# gnss.net
KiCad netlist of a schematic drawn in EAGLE
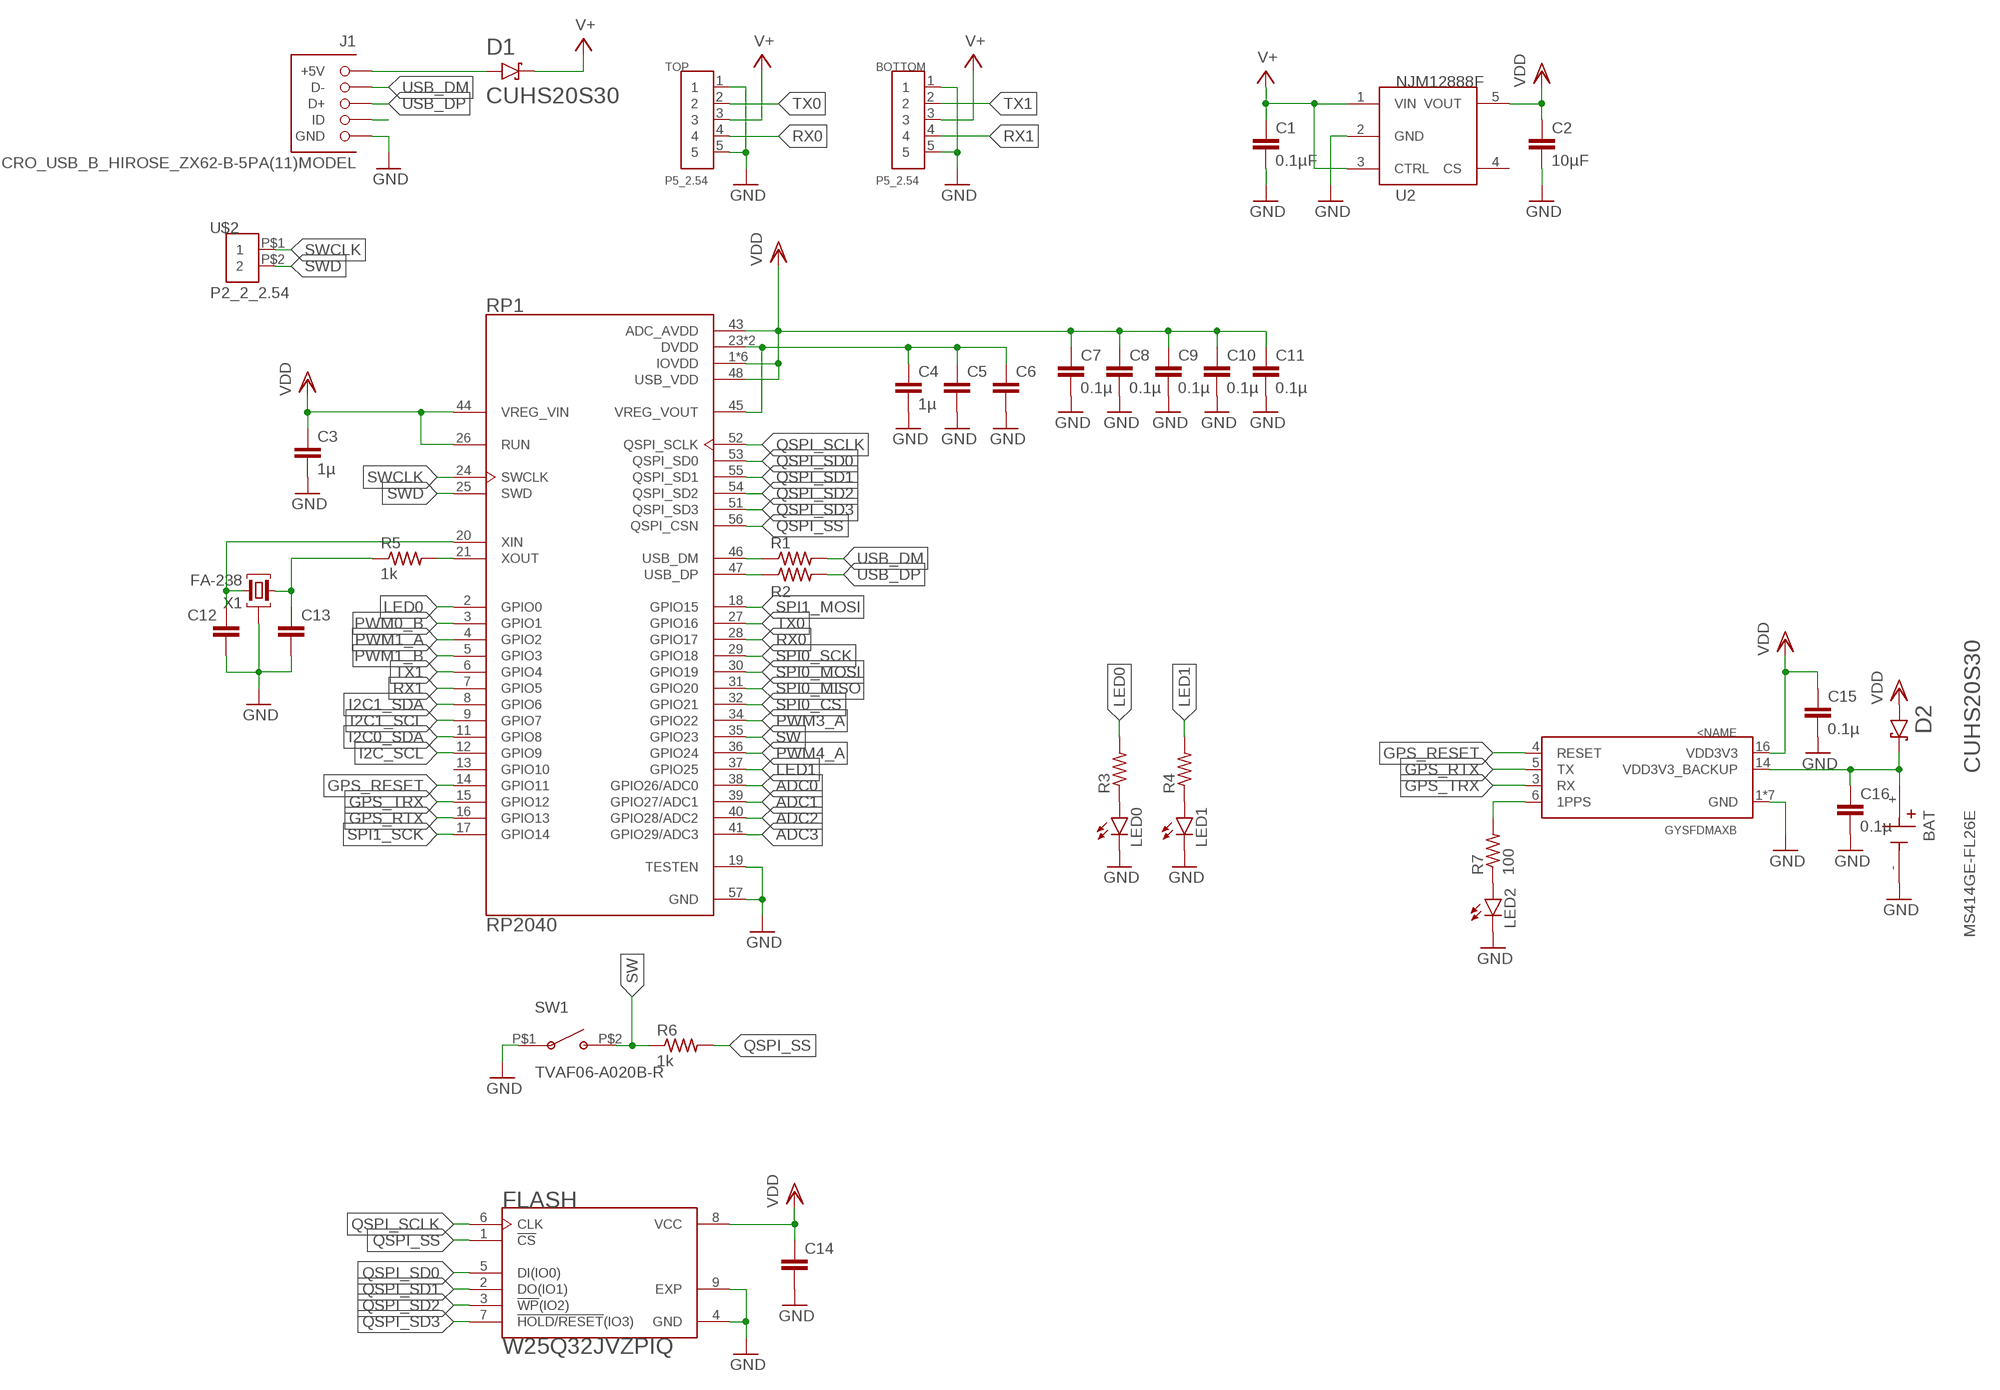
[diagram p0: schematic, sheet 1]

(export (version "E")
  (design (tool "Eeschema 10.0.6"))
  (components
    (comp (ref "BAT")
      (value "MS414GE-FL26E")
      (footprint "eagle-import:BAT_MS414GE-FL26E")
      (fields (field (name "MF") "Seiko"))
      (libsource (lib "eagle-import") (part "MS414GE-FL26E"))
    )
    (comp (ref "BOTTOM")
      (value "P5_2.54")
      (footprint "eagle-import:P5_2.54")
      (libsource (lib "eagle-import") (part "P5_2.54"))
    )
    (comp (ref "C1")
      (value "0.1µF")
      (footprint "eagle-import:C0402")
      (libsource (lib "eagle-import") (part "C-EUC0402"))
    )
    (comp (ref "C2")
      (value "10µF")
      (footprint "eagle-import:C0402")
      (libsource (lib "eagle-import") (part "C-EUC0402"))
    )
    (comp (ref "C3")
      (value "1µ")
      (footprint "eagle-import:C0402")
      (libsource (lib "eagle-import") (part "C-EUC0402"))
    )
    (comp (ref "C4")
      (value "1µ")
      (footprint "eagle-import:C0402")
      (libsource (lib "eagle-import") (part "C-EUC0402"))
    )
    (comp (ref "C5")
      (value "C-EUC0402")
      (footprint "eagle-import:C0402")
      (libsource (lib "eagle-import") (part "C-EUC0402"))
    )
    (comp (ref "C6")
      (value "C-EUC0402")
      (footprint "eagle-import:C0402")
      (libsource (lib "eagle-import") (part "C-EUC0402"))
    )
    (comp (ref "C7")
      (value "0.1µ")
      (footprint "eagle-import:C0402")
      (libsource (lib "eagle-import") (part "C-EUC0402"))
    )
    (comp (ref "C8")
      (value "0.1µ")
      (footprint "eagle-import:C0402")
      (libsource (lib "eagle-import") (part "C-EUC0402"))
    )
    (comp (ref "C9")
      (value "0.1µ")
      (footprint "eagle-import:C0402")
      (libsource (lib "eagle-import") (part "C-EUC0402"))
    )
    (comp (ref "C10")
      (value "0.1µ")
      (footprint "eagle-import:C0402")
      (libsource (lib "eagle-import") (part "C-EUC0402"))
    )
    (comp (ref "C11")
      (value "0.1µ")
      (footprint "eagle-import:C0402")
      (libsource (lib "eagle-import") (part "C-EUC0402"))
    )
    (comp (ref "C12")
      (value "C-EUC0402")
      (footprint "eagle-import:C0402")
      (libsource (lib "eagle-import") (part "C-EUC0402"))
    )
    (comp (ref "C13")
      (value "C-EUC0402")
      (footprint "eagle-import:C0402")
      (libsource (lib "eagle-import") (part "C-EUC0402"))
    )
    (comp (ref "C14")
      (value "C-EUC0402")
      (footprint "eagle-import:C0402")
      (libsource (lib "eagle-import") (part "C-EUC0402"))
    )
    (comp (ref "C15")
      (value "0.1µ")
      (footprint "eagle-import:C0402")
      (libsource (lib "eagle-import") (part "C-EUC0402"))
    )
    (comp (ref "C16")
      (value "0.1µ")
      (footprint "eagle-import:C0402")
      (libsource (lib "eagle-import") (part "C-EUC0402"))
    )
    (comp (ref "D1")
      (value "CUHS20S30")
      (footprint "eagle-import:CUHS20S30")
      (libsource (lib "eagle-import") (part "CUHS20S30"))
    )
    (comp (ref "D2")
      (value "CUHS20S30")
      (footprint "eagle-import:CUHS20S30")
      (libsource (lib "eagle-import") (part "CUHS20S30"))
    )
    (comp (ref "FLASH")
      (value "W25Q32JVZPIQ")
      (footprint "eagle-import:SON127P600X500X80-9N")
      (fields (field (name "MF") "Winbond"))
      (libsource (lib "eagle-import") (part "W25Q32JVZPIQ"))
    )
    (comp (ref "GNSS")
      (value "GYSFDMAXB")
      (footprint "eagle-import:GYSFDMAXB")
      (libsource (lib "eagle-import") (part "GYSFDMAXB"))
    )
    (comp (ref "J1")
      (value "MICRO_USB_B_HIROSE_ZX62-B-5PA(11)MODEL")
      (footprint "eagle-import:GHI-CONNECTORS_10118192-0001LF(MICRO-USB-B-AMPHENOL-FCI)")
      (libsource (lib "eagle-import") (part "MICRO_USB_B_HIROSE_ZX62-B-5PA(11)MODEL"))
    )
    (comp (ref "LED0")
      (value "LEDCHIPLED_0603")
      (footprint "eagle-import:CHIPLED_0603")
      (libsource (lib "eagle-import") (part "LEDCHIPLED_0603"))
    )
    (comp (ref "LED1")
      (value "LEDCHIPLED_0603")
      (footprint "eagle-import:CHIPLED_0603")
      (libsource (lib "eagle-import") (part "LEDCHIPLED_0603"))
    )
    (comp (ref "LED2")
      (value "LEDCHIPLED_0603")
      (footprint "eagle-import:CHIPLED_0603")
      (libsource (lib "eagle-import") (part "LEDCHIPLED_0603"))
    )
    (comp (ref "R1")
      (value "R-US_R0402")
      (footprint "eagle-import:R0402")
      (libsource (lib "eagle-import") (part "R-US_R0402"))
    )
    (comp (ref "R2")
      (value "R-US_R0402")
      (footprint "eagle-import:R0402")
      (libsource (lib "eagle-import") (part "R-US_R0402"))
    )
    (comp (ref "R3")
      (value "R-US_R0402")
      (footprint "eagle-import:R0402")
      (libsource (lib "eagle-import") (part "R-US_R0402"))
    )
    (comp (ref "R4")
      (value "R-US_R0402")
      (footprint "eagle-import:R0402")
      (libsource (lib "eagle-import") (part "R-US_R0402"))
    )
    (comp (ref "R5")
      (value "1k")
      (footprint "eagle-import:R0402")
      (libsource (lib "eagle-import") (part "R-US_R0402"))
    )
    (comp (ref "R6")
      (value "1k")
      (footprint "eagle-import:R0402")
      (libsource (lib "eagle-import") (part "R-US_R0402"))
    )
    (comp (ref "R7")
      (value "100")
      (footprint "eagle-import:R0402")
      (libsource (lib "eagle-import") (part "R-US_R0402"))
    )
    (comp (ref "RP1")
      (value "RP2040")
      (footprint "eagle-import:QFN40P700X700X90-57N")
      (fields (field (name "MF") "Raspberry Pi"))
      (libsource (lib "eagle-import") (part "RP2040"))
    )
    (comp (ref "SW1")
      (value "TVAF06-A020B-R")
      (footprint "eagle-import:TVAF06-A020B-R")
      (libsource (lib "eagle-import") (part "TVAF06-A020B-R"))
    )
    (comp (ref "TOP")
      (value "P5_2.54")
      (footprint "eagle-import:P5_2.54")
      (libsource (lib "eagle-import") (part "P5_2.54"))
    )
    (comp (ref "U$2")
      (value "P2_2_2.54")
      (footprint "eagle-import:P2_2.54")
      (libsource (lib "eagle-import") (part "P2_2_2.54"))
    )
    (comp (ref "U2")
      (value "NJM12888F")
      (footprint "eagle-import:SOT95P240X110-5N")
      (libsource (lib "eagle-import") (part "NJM12888F"))
    )
    (comp (ref "X1")
      (value "FA-238")
      (footprint "eagle-import:FA-238")
      (libsource (lib "eagle-import") (part "FA-238"))
    )
  )
  (nets
    (net (code "1") (name "ADC0") (class "Default")
      (node (ref "RP1") (pin "38") (pinfunction "GPIO26/ADC0_38") (pintype "bidirectional"))
    )
    (net (code "2") (name "ADC1") (class "Default")
      (node (ref "RP1") (pin "39") (pinfunction "GPIO27/ADC1_39") (pintype "bidirectional"))
    )
    (net (code "3") (name "ADC2") (class "Default")
      (node (ref "RP1") (pin "40") (pinfunction "GPIO28/ADC2_40") (pintype "bidirectional"))
    )
    (net (code "4") (name "ADC3") (class "Default")
      (node (ref "RP1") (pin "41") (pinfunction "GPIO29/ADC3_41") (pintype "bidirectional"))
    )
    (net (code "5") (name "GND") (class "Default")
      (node (ref "BAT") (pin "-") (pinfunction "-_-") (pintype "passive"))
      (node (ref "BOTTOM") (pin "1") (pinfunction "1_1") (pintype "bidirectional"))
      (node (ref "BOTTOM") (pin "5") (pinfunction "5_5") (pintype "bidirectional"))
      (node (ref "C1") (pin "2") (pinfunction "2_2") (pintype "passive"))
      (node (ref "C10") (pin "2") (pinfunction "2_2") (pintype "passive"))
      (node (ref "C11") (pin "2") (pinfunction "2_2") (pintype "passive"))
      (node (ref "C12") (pin "2") (pinfunction "2_2") (pintype "passive"))
      (node (ref "C13") (pin "2") (pinfunction "2_2") (pintype "passive"))
      (node (ref "C14") (pin "2") (pinfunction "2_2") (pintype "passive"))
      (node (ref "C15") (pin "2") (pinfunction "2_2") (pintype "passive"))
      (node (ref "C16") (pin "2") (pinfunction "2_2") (pintype "passive"))
      (node (ref "C2") (pin "2") (pinfunction "2_2") (pintype "passive"))
      (node (ref "C3") (pin "2") (pinfunction "2_2") (pintype "passive"))
      (node (ref "C4") (pin "2") (pinfunction "2_2") (pintype "passive"))
      (node (ref "C5") (pin "2") (pinfunction "2_2") (pintype "passive"))
      (node (ref "C6") (pin "2") (pinfunction "2_2") (pintype "passive"))
      (node (ref "C7") (pin "2") (pinfunction "2_2") (pintype "passive"))
      (node (ref "C8") (pin "2") (pinfunction "2_2") (pintype "passive"))
      (node (ref "C9") (pin "2") (pinfunction "2_2") (pintype "passive"))
      (node (ref "FLASH") (pin "4") (pinfunction "GND_4") (pintype "power_in"))
      (node (ref "FLASH") (pin "9") (pinfunction "EXP_9") (pintype "passive"))
      (node (ref "GNSS") (pin "1") (pinfunction "GND_1") (pintype "bidirectional"))
      (node (ref "GNSS") (pin "10") (pinfunction "GND_10") (pintype "bidirectional"))
      (node (ref "GNSS") (pin "12") (pinfunction "GND_12") (pintype "bidirectional"))
      (node (ref "GNSS") (pin "19") (pinfunction "GND_19") (pintype "bidirectional"))
      (node (ref "GNSS") (pin "2") (pinfunction "GND_2") (pintype "bidirectional"))
      (node (ref "GNSS") (pin "20") (pinfunction "GND_20") (pintype "bidirectional"))
      (node (ref "GNSS") (pin "7") (pinfunction "GND_7") (pintype "bidirectional"))
      (node (ref "J1") (pin "CGND1") (pinfunction "GND_CGND1") (pintype "bidirectional"))
      (node (ref "J1") (pin "CGND2") (pinfunction "GND_CGND2") (pintype "bidirectional"))
      (node (ref "J1") (pin "CGND3") (pinfunction "GND_CGND3") (pintype "bidirectional"))
      (node (ref "J1") (pin "CGND4") (pinfunction "GND_CGND4") (pintype "bidirectional"))
      (node (ref "J1") (pin "CGND5") (pinfunction "GND_CGND5") (pintype "bidirectional"))
      (node (ref "J1") (pin "CGND6") (pinfunction "GND_CGND6") (pintype "bidirectional"))
      (node (ref "J1") (pin "GND") (pinfunction "GND_GND") (pintype "bidirectional"))
      (node (ref "LED0") (pin "C") (pinfunction "C_C") (pintype "passive"))
      (node (ref "LED1") (pin "C") (pinfunction "C_C") (pintype "passive"))
      (node (ref "LED2") (pin "C") (pinfunction "C_C") (pintype "passive"))
      (node (ref "RP1") (pin "19") (pinfunction "TESTEN_19") (pintype "passive"))
      (node (ref "RP1") (pin "57") (pinfunction "GND_57") (pintype "power_in"))
      (node (ref "SW1") (pin "P$1") (pinfunction "A_P$1") (pintype "bidirectional"))
      (node (ref "TOP") (pin "1") (pinfunction "1_1") (pintype "bidirectional"))
      (node (ref "TOP") (pin "5") (pinfunction "5_5") (pintype "bidirectional"))
      (node (ref "U2") (pin "2") (pinfunction "GND_2") (pintype "power_in"))
      (node (ref "X1") (pin "2") (pinfunction "G_2") (pintype "passive"))
      (node (ref "X1") (pin "4") (pinfunction "G_4") (pintype "passive"))
    )
    (net (code "6") (name "GPS_RESET") (class "Default")
      (node (ref "GNSS") (pin "4") (pinfunction "RESET_4") (pintype "bidirectional"))
      (node (ref "RP1") (pin "14") (pinfunction "GPIO11_14") (pintype "bidirectional"))
    )
    (net (code "7") (name "GPS_RTX") (class "Default")
      (node (ref "GNSS") (pin "5") (pinfunction "TX_5") (pintype "bidirectional"))
      (node (ref "RP1") (pin "16") (pinfunction "GPIO13_16") (pintype "bidirectional"))
    )
    (net (code "8") (name "GPS_TRX") (class "Default")
      (node (ref "GNSS") (pin "3") (pinfunction "RX_3") (pintype "bidirectional"))
      (node (ref "RP1") (pin "15") (pinfunction "GPIO12_15") (pintype "bidirectional"))
    )
    (net (code "9") (name "I2C0_SDA") (class "Default")
      (node (ref "RP1") (pin "11") (pinfunction "GPIO8_11") (pintype "bidirectional"))
    )
    (net (code "10") (name "I2C1_SCL") (class "Default")
      (node (ref "RP1") (pin "9") (pinfunction "GPIO7_9") (pintype "bidirectional"))
    )
    (net (code "11") (name "I2C1_SDA") (class "Default")
      (node (ref "RP1") (pin "8") (pinfunction "GPIO6_8") (pintype "bidirectional"))
    )
    (net (code "12") (name "I2C_SCL") (class "Default")
      (node (ref "RP1") (pin "12") (pinfunction "GPIO9_12") (pintype "bidirectional"))
    )
    (net (code "13") (name "LED0") (class "Default")
      (node (ref "R3") (pin "2") (pinfunction "2_2") (pintype "passive"))
      (node (ref "RP1") (pin "2") (pinfunction "GPIO0_2") (pintype "bidirectional"))
    )
    (net (code "14") (name "LED1") (class "Default")
      (node (ref "R4") (pin "2") (pinfunction "2_2") (pintype "passive"))
      (node (ref "RP1") (pin "37") (pinfunction "GPIO25_37") (pintype "bidirectional"))
    )
    (net (code "15") (name "Net-(C13-Pad1)") (class "Default")
      (node (ref "C13") (pin "1") (pinfunction "1_1") (pintype "passive"))
      (node (ref "R5") (pin "1") (pinfunction "1_1") (pintype "passive"))
      (node (ref "X1") (pin "1") (pinfunction "1_1") (pintype "passive"))
    )
    (net (code "16") (name "Net-(GNSS-1PPS)") (class "Default")
      (node (ref "GNSS") (pin "6") (pinfunction "1PPS_6") (pintype "bidirectional"))
      (node (ref "R7") (pin "2") (pinfunction "2_2") (pintype "passive"))
    )
    (net (code "17") (name "Net-(GNSS-VDD3V3_BACKUP)") (class "Default")
      (node (ref "BAT") (pin "+") (pinfunction "+_+") (pintype "passive"))
      (node (ref "C16") (pin "1") (pinfunction "1_1") (pintype "passive"))
      (node (ref "D2") (pin "C") (pinfunction "C_C") (pintype "bidirectional"))
      (node (ref "GNSS") (pin "14") (pinfunction "VDD3V3_BACKUP_14") (pintype "bidirectional"))
    )
    (net (code "18") (name "Net-(J1-+5V)") (class "Default")
      (node (ref "D1") (pin "A") (pinfunction "A_A") (pintype "bidirectional"))
      (node (ref "J1") (pin "VBUS") (pinfunction "+5V_VBUS") (pintype "bidirectional"))
    )
    (net (code "19") (name "Net-(LED0-PadA)") (class "Default")
      (node (ref "LED0") (pin "A") (pinfunction "A_A") (pintype "passive"))
      (node (ref "R3") (pin "1") (pinfunction "1_1") (pintype "passive"))
    )
    (net (code "20") (name "Net-(LED1-PadA)") (class "Default")
      (node (ref "LED1") (pin "A") (pinfunction "A_A") (pintype "passive"))
      (node (ref "R4") (pin "1") (pinfunction "1_1") (pintype "passive"))
    )
    (net (code "21") (name "Net-(LED2-PadA)") (class "Default")
      (node (ref "LED2") (pin "A") (pinfunction "A_A") (pintype "passive"))
      (node (ref "R7") (pin "1") (pinfunction "1_1") (pintype "passive"))
    )
    (net (code "22") (name "Net-(RP1-USB_DM)") (class "Default")
      (node (ref "R1") (pin "1") (pinfunction "1_1") (pintype "passive"))
      (node (ref "RP1") (pin "46") (pinfunction "USB_DM_46") (pintype "bidirectional"))
    )
    (net (code "23") (name "Net-(RP1-USB_DP)") (class "Default")
      (node (ref "R2") (pin "1") (pinfunction "1_1") (pintype "passive"))
      (node (ref "RP1") (pin "47") (pinfunction "USB_DP_47") (pintype "bidirectional"))
    )
    (net (code "24") (name "Net-(RP1-VREG_VOUT)") (class "Default")
      (node (ref "C4") (pin "1") (pinfunction "1_1") (pintype "passive"))
      (node (ref "C5") (pin "1") (pinfunction "1_1") (pintype "passive"))
      (node (ref "C6") (pin "1") (pinfunction "1_1") (pintype "passive"))
      (node (ref "RP1") (pin "23") (pinfunction "DVDD_23") (pintype "power_in"))
      (node (ref "RP1") (pin "45") (pinfunction "VREG_VOUT_45") (pintype "output"))
      (node (ref "RP1") (pin "50") (pinfunction "DVDD_50") (pintype "power_in"))
    )
    (net (code "25") (name "Net-(RP1-XIN)") (class "Default")
      (node (ref "C12") (pin "1") (pinfunction "1_1") (pintype "passive"))
      (node (ref "RP1") (pin "20") (pinfunction "XIN_20") (pintype "input"))
      (node (ref "X1") (pin "3") (pinfunction "2_3") (pintype "passive"))
    )
    (net (code "26") (name "Net-(RP1-XOUT)") (class "Default")
      (node (ref "R5") (pin "2") (pinfunction "2_2") (pintype "passive"))
      (node (ref "RP1") (pin "21") (pinfunction "XOUT_21") (pintype "output"))
    )
    (net (code "27") (name "PWM0_B") (class "Default")
      (node (ref "RP1") (pin "3") (pinfunction "GPIO1_3") (pintype "bidirectional"))
    )
    (net (code "28") (name "PWM1_A") (class "Default")
      (node (ref "RP1") (pin "4") (pinfunction "GPIO2_4") (pintype "bidirectional"))
    )
    (net (code "29") (name "PWM1_B") (class "Default")
      (node (ref "RP1") (pin "5") (pinfunction "GPIO3_5") (pintype "bidirectional"))
    )
    (net (code "30") (name "PWM3_A") (class "Default")
      (node (ref "RP1") (pin "34") (pinfunction "GPIO22_34") (pintype "bidirectional"))
    )
    (net (code "31") (name "PWM4_A") (class "Default")
      (node (ref "RP1") (pin "36") (pinfunction "GPIO24_36") (pintype "bidirectional"))
    )
    (net (code "32") (name "QSPI_SCLK") (class "Default")
      (node (ref "FLASH") (pin "6") (pinfunction "CLK_6") (pintype "input"))
      (node (ref "RP1") (pin "52") (pinfunction "QSPI_SCLK_52") (pintype "bidirectional"))
    )
    (net (code "33") (name "QSPI_SD0") (class "Default")
      (node (ref "FLASH") (pin "5") (pinfunction "DI(IO0)_5") (pintype "bidirectional"))
      (node (ref "RP1") (pin "53") (pinfunction "QSPI_SD0_53") (pintype "bidirectional"))
    )
    (net (code "34") (name "QSPI_SD1") (class "Default")
      (node (ref "FLASH") (pin "2") (pinfunction "DO(IO1)_2") (pintype "bidirectional"))
      (node (ref "RP1") (pin "55") (pinfunction "QSPI_SD1_55") (pintype "bidirectional"))
    )
    (net (code "35") (name "QSPI_SD2") (class "Default")
      (node (ref "FLASH") (pin "3") (pinfunction "~{WP}(IO2)_3") (pintype "bidirectional"))
      (node (ref "RP1") (pin "54") (pinfunction "QSPI_SD2_54") (pintype "bidirectional"))
    )
    (net (code "36") (name "QSPI_SD3") (class "Default")
      (node (ref "FLASH") (pin "7") (pinfunction "~{HOLD/RESET}(IO3)_7") (pintype "bidirectional"))
      (node (ref "RP1") (pin "51") (pinfunction "QSPI_SD3_51") (pintype "bidirectional"))
    )
    (net (code "37") (name "QSPI_SS") (class "Default")
      (node (ref "FLASH") (pin "1") (pinfunction "~{CS}_1") (pintype "input"))
      (node (ref "R6") (pin "2") (pinfunction "2_2") (pintype "passive"))
      (node (ref "RP1") (pin "56") (pinfunction "QSPI_CSN_56") (pintype "bidirectional"))
    )
    (net (code "38") (name "RX0") (class "Default")
      (node (ref "RP1") (pin "28") (pinfunction "GPIO17_28") (pintype "bidirectional"))
      (node (ref "TOP") (pin "4") (pinfunction "4_4") (pintype "bidirectional"))
    )
    (net (code "39") (name "RX1") (class "Default")
      (node (ref "BOTTOM") (pin "4") (pinfunction "4_4") (pintype "bidirectional"))
      (node (ref "RP1") (pin "7") (pinfunction "GPIO5_7") (pintype "bidirectional"))
    )
    (net (code "40") (name "SPI0_CS") (class "Default")
      (node (ref "RP1") (pin "32") (pinfunction "GPIO21_32") (pintype "bidirectional"))
    )
    (net (code "41") (name "SPI0_MISO") (class "Default")
      (node (ref "RP1") (pin "31") (pinfunction "GPIO20_31") (pintype "bidirectional"))
    )
    (net (code "42") (name "SPI0_MOSI") (class "Default")
      (node (ref "RP1") (pin "30") (pinfunction "GPIO19_30") (pintype "bidirectional"))
    )
    (net (code "43") (name "SPI0_SCK") (class "Default")
      (node (ref "RP1") (pin "29") (pinfunction "GPIO18_29") (pintype "bidirectional"))
    )
    (net (code "44") (name "SPI1_MOSI") (class "Default")
      (node (ref "RP1") (pin "18") (pinfunction "GPIO15_18") (pintype "bidirectional"))
    )
    (net (code "45") (name "SPI1_SCK") (class "Default")
      (node (ref "RP1") (pin "17") (pinfunction "GPIO14_17") (pintype "bidirectional"))
    )
    (net (code "46") (name "SW") (class "Default")
      (node (ref "R6") (pin "1") (pinfunction "1_1") (pintype "passive"))
      (node (ref "RP1") (pin "35") (pinfunction "GPIO23_35") (pintype "bidirectional"))
      (node (ref "SW1") (pin "P$2") (pinfunction "B_P$2") (pintype "bidirectional"))
    )
    (net (code "47") (name "SWCLK") (class "Default")
      (node (ref "RP1") (pin "24") (pinfunction "SWCLK_24") (pintype "input"))
      (node (ref "U$2") (pin "P$1") (pinfunction "1_P$1") (pintype "bidirectional"))
    )
    (net (code "48") (name "SWD") (class "Default")
      (node (ref "RP1") (pin "25") (pinfunction "SWD_25") (pintype "bidirectional"))
      (node (ref "U$2") (pin "P$2") (pinfunction "2_P$2") (pintype "bidirectional"))
    )
    (net (code "49") (name "TX0") (class "Default")
      (node (ref "RP1") (pin "27") (pinfunction "GPIO16_27") (pintype "bidirectional"))
      (node (ref "TOP") (pin "2") (pinfunction "2_2") (pintype "bidirectional"))
    )
    (net (code "50") (name "TX1") (class "Default")
      (node (ref "BOTTOM") (pin "2") (pinfunction "2_2") (pintype "bidirectional"))
      (node (ref "RP1") (pin "6") (pinfunction "GPIO4_6") (pintype "bidirectional"))
    )
    (net (code "51") (name "USB_DM") (class "Default")
      (node (ref "J1") (pin "D-") (pinfunction "D-_D-") (pintype "bidirectional"))
      (node (ref "R1") (pin "2") (pinfunction "2_2") (pintype "passive"))
    )
    (net (code "52") (name "USB_DP") (class "Default")
      (node (ref "J1") (pin "D+") (pinfunction "D+_D+") (pintype "bidirectional"))
      (node (ref "R2") (pin "2") (pinfunction "2_2") (pintype "passive"))
    )
    (net (code "53") (name "V+") (class "Default")
      (node (ref "BOTTOM") (pin "3") (pinfunction "3_3") (pintype "bidirectional"))
      (node (ref "C1") (pin "1") (pinfunction "1_1") (pintype "passive"))
      (node (ref "D1") (pin "C") (pinfunction "C_C") (pintype "bidirectional"))
      (node (ref "TOP") (pin "3") (pinfunction "3_3") (pintype "bidirectional"))
      (node (ref "U2") (pin "1") (pinfunction "VIN_1") (pintype "power_in"))
      (node (ref "U2") (pin "3") (pinfunction "CTRL_3") (pintype "input"))
    )
    (net (code "54") (name "VDD") (class "Default")
      (node (ref "C10") (pin "1") (pinfunction "1_1") (pintype "passive"))
      (node (ref "C11") (pin "1") (pinfunction "1_1") (pintype "passive"))
      (node (ref "C14") (pin "1") (pinfunction "1_1") (pintype "passive"))
      (node (ref "C15") (pin "1") (pinfunction "1_1") (pintype "passive"))
      (node (ref "C2") (pin "1") (pinfunction "1_1") (pintype "passive"))
      (node (ref "C3") (pin "1") (pinfunction "1_1") (pintype "passive"))
      (node (ref "C7") (pin "1") (pinfunction "1_1") (pintype "passive"))
      (node (ref "C8") (pin "1") (pinfunction "1_1") (pintype "passive"))
      (node (ref "C9") (pin "1") (pinfunction "1_1") (pintype "passive"))
      (node (ref "D2") (pin "A") (pinfunction "A_A") (pintype "bidirectional"))
      (node (ref "FLASH") (pin "8") (pinfunction "VCC_8") (pintype "power_in"))
      (node (ref "GNSS") (pin "16") (pinfunction "VDD3V3_16") (pintype "bidirectional"))
      (node (ref "RP1") (pin "1") (pinfunction "IOVDD_1") (pintype "power_in"))
      (node (ref "RP1") (pin "10") (pinfunction "IOVDD_10") (pintype "power_in"))
      (node (ref "RP1") (pin "22") (pinfunction "IOVDD_22") (pintype "power_in"))
      (node (ref "RP1") (pin "26") (pinfunction "RUN_26") (pintype "input"))
      (node (ref "RP1") (pin "33") (pinfunction "IOVDD_33") (pintype "power_in"))
      (node (ref "RP1") (pin "42") (pinfunction "IOVDD_42") (pintype "power_in"))
      (node (ref "RP1") (pin "43") (pinfunction "ADC_AVDD_43") (pintype "power_in"))
      (node (ref "RP1") (pin "44") (pinfunction "VREG_VIN_44") (pintype "input"))
      (node (ref "RP1") (pin "48") (pinfunction "USB_VDD_48") (pintype "power_in"))
      (node (ref "RP1") (pin "49") (pinfunction "IOVDD_49") (pintype "power_in"))
      (node (ref "U2") (pin "5") (pinfunction "VOUT_5") (pintype "power_in"))
    )
    (net (code "55") (name "unconnected-(J1-PadID)") (class "Default")
      (node (ref "J1") (pin "ID") (pinfunction "ID_ID") (pintype "bidirectional"))
    )
    (net (code "56") (name "unconnected-(RP1-GPIO10-Pad13)") (class "Default")
      (node (ref "RP1") (pin "13") (pinfunction "GPIO10_13") (pintype "bidirectional"))
    )
    (net (code "57") (name "unconnected-(U2-CS-Pad4)") (class "Default")
      (node (ref "U2") (pin "4") (pinfunction "CS_4") (pintype "input"))
    )
  )
)
